# ENC28J60_Wing.net
KiCad netlist of a schematic drawn in EAGLE
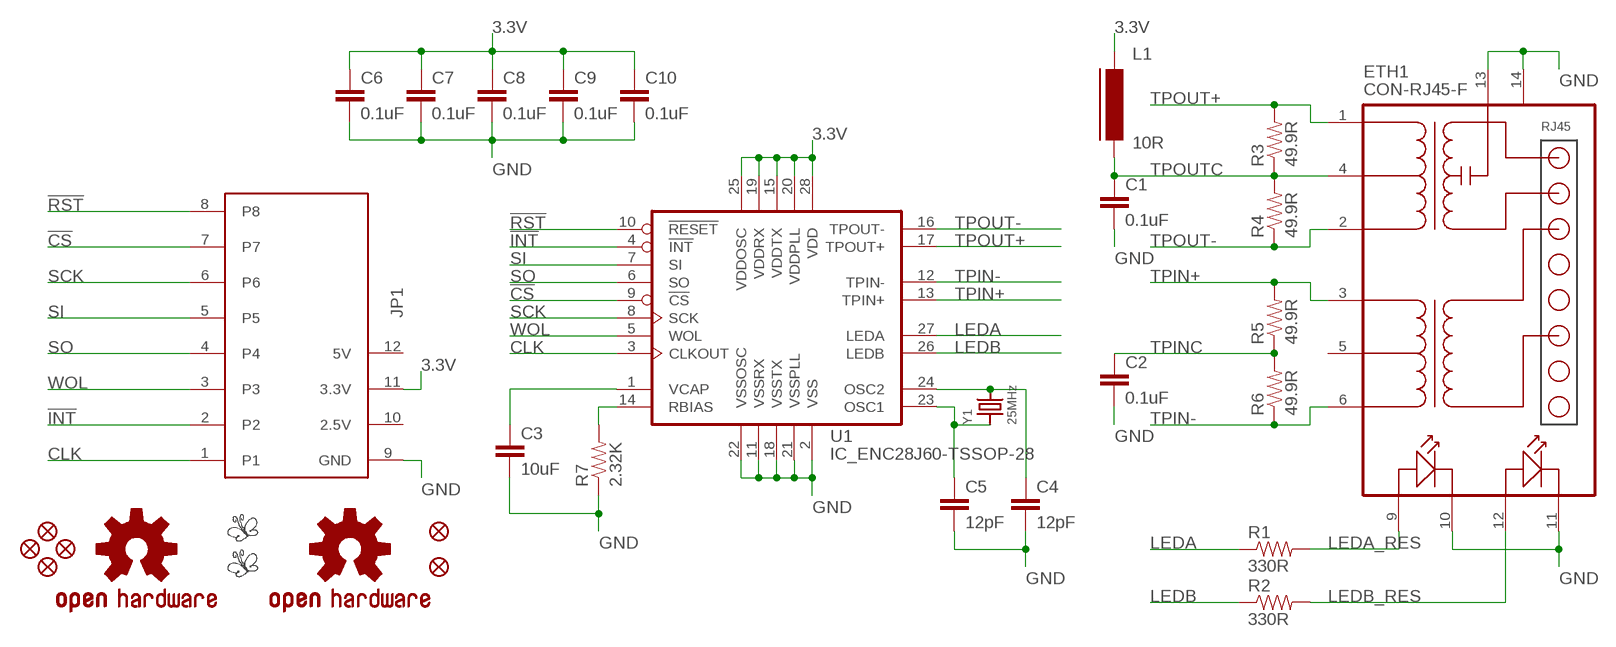
[diagram p0: schematic, sheet 1]

(export (version "E")
  (design (tool "Eeschema 10.0.6"))
  (components
    (comp (ref "C1")
      (value "0.1uF")
      (footprint "eagle-import:0402-CAP")
      (libsource (lib "eagle-import") (part "CAP0402-CAP"))
    )
    (comp (ref "C2")
      (value "0.1uF")
      (footprint "eagle-import:0402-CAP")
      (libsource (lib "eagle-import") (part "CAP0402-CAP"))
    )
    (comp (ref "C3")
      (value "10uF")
      (footprint "eagle-import:1206")
      (libsource (lib "eagle-import") (part "CAP1206"))
    )
    (comp (ref "C4")
      (value "12pF")
      (footprint "eagle-import:0402-CAP")
      (libsource (lib "eagle-import") (part "CAP0402-CAP"))
    )
    (comp (ref "C5")
      (value "12pF")
      (footprint "eagle-import:0402-CAP")
      (libsource (lib "eagle-import") (part "CAP0402-CAP"))
    )
    (comp (ref "C6")
      (value "0.1uF")
      (footprint "eagle-import:0402-CAP")
      (libsource (lib "eagle-import") (part "CAP0402-CAP"))
    )
    (comp (ref "C7")
      (value "0.1uF")
      (footprint "eagle-import:0402-CAP")
      (libsource (lib "eagle-import") (part "CAP0402-CAP"))
    )
    (comp (ref "C8")
      (value "0.1uF")
      (footprint "eagle-import:0402-CAP")
      (libsource (lib "eagle-import") (part "CAP0402-CAP"))
    )
    (comp (ref "C9")
      (value "0.1uF")
      (footprint "eagle-import:0402-CAP")
      (libsource (lib "eagle-import") (part "CAP0402-CAP"))
    )
    (comp (ref "C10")
      (value "0.1uF")
      (footprint "eagle-import:0402-CAP")
      (libsource (lib "eagle-import") (part "CAP0402-CAP"))
    )
    (comp (ref "ETH1")
      (value "CON-RJ45-F")
      (footprint "eagle-import:HR911105A")
      (libsource (lib "eagle-import") (part "CON-RJ45-F"))
    )
    (comp (ref "FID1")
      (value "FIDUCIALUFIDUCIAL")
      (footprint "eagle-import:MICRO-FIDUCIAL")
      (libsource (lib "eagle-import") (part "FIDUCIALUFIDUCIAL"))
    )
    (comp (ref "FID2")
      (value "FIDUCIALUFIDUCIAL")
      (footprint "eagle-import:MICRO-FIDUCIAL")
      (libsource (lib "eagle-import") (part "FIDUCIALUFIDUCIAL"))
    )
    (comp (ref "FID3")
      (value "FIDUCIALUFIDUCIAL")
      (footprint "eagle-import:MICRO-FIDUCIAL")
      (libsource (lib "eagle-import") (part "FIDUCIALUFIDUCIAL"))
    )
    (comp (ref "FID4")
      (value "FIDUCIALUFIDUCIAL")
      (footprint "eagle-import:MICRO-FIDUCIAL")
      (libsource (lib "eagle-import") (part "FIDUCIALUFIDUCIAL"))
    )
    (comp (ref "FID5")
      (value "FIDUCIALUFIDUCIAL")
      (footprint "eagle-import:MICRO-FIDUCIAL")
      (libsource (lib "eagle-import") (part "FIDUCIALUFIDUCIAL"))
    )
    (comp (ref "FID6")
      (value "FIDUCIALUFIDUCIAL")
      (footprint "eagle-import:MICRO-FIDUCIAL")
      (libsource (lib "eagle-import") (part "FIDUCIALUFIDUCIAL"))
    )
    (comp (ref "JP1")
      (value "PAPILIO-WING-8BITS")
      (footprint "eagle-import:PAPILIO-WING-8BITS")
      (libsource (lib "eagle-import") (part "PAPILIO-WING-8BITS"))
    )
    (comp (ref "L1")
      (value "10R")
      (footprint "eagle-import:FB402")
      (libsource (lib "eagle-import") (part "FERRITE-0402"))
    )
    (comp (ref "LOGO1")
      (value "BUTTERFLY_LOGO")
      (footprint "eagle-import:BUTTERFLY_LOGO")
      (libsource (lib "eagle-import") (part "BUTTERFLY_LOGO"))
    )
    (comp (ref "LOGO2")
      (value "BUTTERFLY_LOGO")
      (footprint "eagle-import:BUTTERFLY_LOGO")
      (libsource (lib "eagle-import") (part "BUTTERFLY_LOGO"))
    )
    (comp (ref "R1")
      (value "330R")
      (footprint "eagle-import:0402-RES")
      (libsource (lib "eagle-import") (part "RESISTOR0402-RES"))
    )
    (comp (ref "R2")
      (value "330R")
      (footprint "eagle-import:0402-RES")
      (libsource (lib "eagle-import") (part "RESISTOR0402-RES"))
    )
    (comp (ref "R3")
      (value "49.9R")
      (footprint "eagle-import:0402-RES")
      (libsource (lib "eagle-import") (part "RESISTOR0402-RES"))
    )
    (comp (ref "R4")
      (value "49.9R")
      (footprint "eagle-import:0402-RES")
      (libsource (lib "eagle-import") (part "RESISTOR0402-RES"))
    )
    (comp (ref "R5")
      (value "49.9R")
      (footprint "eagle-import:0402-RES")
      (libsource (lib "eagle-import") (part "RESISTOR0402-RES"))
    )
    (comp (ref "R6")
      (value "49.9R")
      (footprint "eagle-import:0402-RES")
      (libsource (lib "eagle-import") (part "RESISTOR0402-RES"))
    )
    (comp (ref "R7")
      (value "2.32K")
      (footprint "eagle-import:0402-RES")
      (libsource (lib "eagle-import") (part "RESISTOR0402-RES"))
    )
    (comp (ref "U$2")
      (value "OSHW-LOGOS")
      (footprint "eagle-import:OSHW-LOGO-S")
      (libsource (lib "eagle-import") (part "OSHW-LOGOS"))
    )
    (comp (ref "U$3")
      (value "OSHW-LOGOS")
      (footprint "eagle-import:OSHW-LOGO-S")
      (libsource (lib "eagle-import") (part "OSHW-LOGOS"))
    )
    (comp (ref "U1")
      (value "IC_ENC28J60-TSSOP-28")
      (footprint "eagle-import:TSSOP-28")
      (libsource (lib "eagle-import") (part "IC_ENC28J60-TSSOP-28"))
    )
    (comp (ref "Y1")
      (value "25MHz")
      (footprint "eagle-import:CRYSTAL_2.5X2")
      (libsource (lib "eagle-import") (part "CRYSTAL2.5X2.0MM"))
    )
  )
  (nets
    (net (code "1") (name "/3.3V") (class "Default")
      (node (ref "C10") (pin "1") (pinfunction "1_1") (pintype "passive"))
      (node (ref "C6") (pin "1") (pinfunction "1_1") (pintype "passive"))
      (node (ref "C7") (pin "1") (pinfunction "1_1") (pintype "passive"))
      (node (ref "C8") (pin "1") (pinfunction "1_1") (pintype "passive"))
      (node (ref "C9") (pin "1") (pinfunction "1_1") (pintype "passive"))
      (node (ref "JP1") (pin "11") (pinfunction "3.3V_11") (pintype "bidirectional"))
      (node (ref "L1") (pin "1") (pinfunction "1_1") (pintype "passive"))
      (node (ref "U1") (pin "15") (pinfunction "VDDTX_15") (pintype "power_in"))
      (node (ref "U1") (pin "19") (pinfunction "VDDRX_19") (pintype "power_in"))
      (node (ref "U1") (pin "20") (pinfunction "VDDPLL_20") (pintype "power_in"))
      (node (ref "U1") (pin "25") (pinfunction "VDDOSC_25") (pintype "power_in"))
      (node (ref "U1") (pin "28") (pinfunction "VDD_28") (pintype "power_in"))
    )
    (net (code "2") (name "/CLK") (class "Default")
      (node (ref "JP1") (pin "1") (pinfunction "P1_1") (pintype "bidirectional"))
      (node (ref "U1") (pin "3") (pinfunction "CLKOUT_3") (pintype "output"))
    )
    (net (code "3") (name "/GND") (class "Default")
      (node (ref "C1") (pin "2") (pinfunction "2_2") (pintype "passive"))
      (node (ref "C10") (pin "2") (pinfunction "2_2") (pintype "passive"))
      (node (ref "C2") (pin "2") (pinfunction "2_2") (pintype "passive"))
      (node (ref "C3") (pin "2") (pinfunction "2_2") (pintype "passive"))
      (node (ref "C4") (pin "2") (pinfunction "2_2") (pintype "passive"))
      (node (ref "C5") (pin "2") (pinfunction "2_2") (pintype "passive"))
      (node (ref "C6") (pin "2") (pinfunction "2_2") (pintype "passive"))
      (node (ref "C7") (pin "2") (pinfunction "2_2") (pintype "passive"))
      (node (ref "C8") (pin "2") (pinfunction "2_2") (pintype "passive"))
      (node (ref "C9") (pin "2") (pinfunction "2_2") (pintype "passive"))
      (node (ref "ETH1") (pin "10") (pinfunction "10_10") (pintype "bidirectional"))
      (node (ref "ETH1") (pin "11") (pinfunction "11_11") (pintype "bidirectional"))
      (node (ref "ETH1") (pin "13") (pinfunction "13_13") (pintype "bidirectional"))
      (node (ref "ETH1") (pin "14") (pinfunction "14_14") (pintype "bidirectional"))
      (node (ref "JP1") (pin "9") (pinfunction "GND_9") (pintype "bidirectional"))
      (node (ref "R7") (pin "1") (pinfunction "1_1") (pintype "passive"))
      (node (ref "U1") (pin "11") (pinfunction "VSSRX_11") (pintype "power_in"))
      (node (ref "U1") (pin "18") (pinfunction "VSSTX_18") (pintype "power_in"))
      (node (ref "U1") (pin "2") (pinfunction "VSS_2") (pintype "power_in"))
      (node (ref "U1") (pin "21") (pinfunction "VSSPLL_21") (pintype "power_in"))
      (node (ref "U1") (pin "22") (pinfunction "VSSOSC_22") (pintype "power_in"))
    )
    (net (code "4") (name "/LEDA") (class "Default")
      (node (ref "R1") (pin "1") (pinfunction "1_1") (pintype "passive"))
      (node (ref "U1") (pin "27") (pinfunction "LEDA_27") (pintype "output"))
    )
    (net (code "5") (name "/LEDA_RES") (class "Default")
      (node (ref "ETH1") (pin "9") (pinfunction "9_9") (pintype "bidirectional"))
      (node (ref "R1") (pin "2") (pinfunction "2_2") (pintype "passive"))
    )
    (net (code "6") (name "/LEDB") (class "Default")
      (node (ref "R2") (pin "1") (pinfunction "1_1") (pintype "passive"))
      (node (ref "U1") (pin "26") (pinfunction "LEDB_26") (pintype "output"))
    )
    (net (code "7") (name "/LEDB_RES") (class "Default")
      (node (ref "ETH1") (pin "12") (pinfunction "12_12") (pintype "bidirectional"))
      (node (ref "R2") (pin "2") (pinfunction "2_2") (pintype "passive"))
    )
    (net (code "8") (name "/SCK") (class "Default")
      (node (ref "JP1") (pin "6") (pinfunction "P6_6") (pintype "bidirectional"))
      (node (ref "U1") (pin "8") (pinfunction "SCK_8") (pintype "input"))
    )
    (net (code "9") (name "/SI") (class "Default")
      (node (ref "JP1") (pin "5") (pinfunction "P5_5") (pintype "bidirectional"))
      (node (ref "U1") (pin "7") (pinfunction "SI_7") (pintype "input"))
    )
    (net (code "10") (name "/SO") (class "Default")
      (node (ref "JP1") (pin "4") (pinfunction "P4_4") (pintype "bidirectional"))
      (node (ref "U1") (pin "6") (pinfunction "SO_6") (pintype "output"))
    )
    (net (code "11") (name "/TPIN+") (class "Default")
      (node (ref "ETH1") (pin "3") (pinfunction "3_3") (pintype "bidirectional"))
      (node (ref "R5") (pin "2") (pinfunction "2_2") (pintype "passive"))
      (node (ref "U1") (pin "13") (pinfunction "TPIN+_13") (pintype "input"))
    )
    (net (code "12") (name "/TPIN-") (class "Default")
      (node (ref "ETH1") (pin "6") (pinfunction "6_6") (pintype "bidirectional"))
      (node (ref "R6") (pin "1") (pinfunction "1_1") (pintype "passive"))
      (node (ref "U1") (pin "12") (pinfunction "TPIN-_12") (pintype "input"))
    )
    (net (code "13") (name "/TPINC") (class "Default")
      (node (ref "C2") (pin "1") (pinfunction "1_1") (pintype "passive"))
      (node (ref "R5") (pin "1") (pinfunction "1_1") (pintype "passive"))
      (node (ref "R6") (pin "2") (pinfunction "2_2") (pintype "passive"))
    )
    (net (code "14") (name "/TPOUT+") (class "Default")
      (node (ref "ETH1") (pin "1") (pinfunction "1_1") (pintype "bidirectional"))
      (node (ref "R3") (pin "2") (pinfunction "2_2") (pintype "passive"))
      (node (ref "U1") (pin "17") (pinfunction "TPOUT+_17") (pintype "output"))
    )
    (net (code "15") (name "/TPOUT-") (class "Default")
      (node (ref "ETH1") (pin "2") (pinfunction "2_2") (pintype "bidirectional"))
      (node (ref "R4") (pin "1") (pinfunction "1_1") (pintype "passive"))
      (node (ref "U1") (pin "16") (pinfunction "TPOUT-_16") (pintype "output"))
    )
    (net (code "16") (name "/TPOUTC") (class "Default")
      (node (ref "C1") (pin "1") (pinfunction "1_1") (pintype "passive"))
      (node (ref "ETH1") (pin "4") (pinfunction "4_4") (pintype "bidirectional"))
      (node (ref "L1") (pin "2") (pinfunction "2_2") (pintype "passive"))
      (node (ref "R3") (pin "1") (pinfunction "1_1") (pintype "passive"))
      (node (ref "R4") (pin "2") (pinfunction "2_2") (pintype "passive"))
    )
    (net (code "17") (name "/WOL") (class "Default")
      (node (ref "JP1") (pin "3") (pinfunction "P3_3") (pintype "bidirectional"))
      (node (ref "U1") (pin "5") (pinfunction "WOL_5") (pintype "bidirectional"))
    )
    (net (code "18") (name "/~{CS}") (class "Default")
      (node (ref "JP1") (pin "7") (pinfunction "P7_7") (pintype "bidirectional"))
      (node (ref "U1") (pin "9") (pinfunction "~{CS}_9") (pintype "input"))
    )
    (net (code "19") (name "/~{INT}") (class "Default")
      (node (ref "JP1") (pin "2") (pinfunction "P2_2") (pintype "bidirectional"))
      (node (ref "U1") (pin "4") (pinfunction "~{INT}_4") (pintype "output"))
    )
    (net (code "20") (name "/~{RST}") (class "Default")
      (node (ref "JP1") (pin "8") (pinfunction "P8_8") (pintype "bidirectional"))
      (node (ref "U1") (pin "10") (pinfunction "~{RESET}_10") (pintype "input"))
    )
    (net (code "21") (name "Net-(U1-OSC1)") (class "Default")
      (node (ref "C5") (pin "1") (pinfunction "1_1") (pintype "passive"))
      (node (ref "U1") (pin "23") (pinfunction "OSC1_23") (pintype "input"))
      (node (ref "Y1") (pin "1") (pinfunction "1_1") (pintype "passive"))
    )
    (net (code "22") (name "Net-(U1-OSC2)") (class "Default")
      (node (ref "C4") (pin "1") (pinfunction "1_1") (pintype "passive"))
      (node (ref "U1") (pin "24") (pinfunction "OSC2_24") (pintype "output"))
      (node (ref "Y1") (pin "3") (pinfunction "2_3") (pintype "passive"))
    )
    (net (code "23") (name "Net-(U1-RBIAS)") (class "Default")
      (node (ref "R7") (pin "2") (pinfunction "2_2") (pintype "passive"))
      (node (ref "U1") (pin "14") (pinfunction "RBIAS_14") (pintype "input"))
    )
    (net (code "24") (name "Net-(U1-VCAP)") (class "Default")
      (node (ref "C3") (pin "1") (pinfunction "1_1") (pintype "passive"))
      (node (ref "U1") (pin "1") (pinfunction "VCAP_1") (pintype "input"))
    )
    (net (code "25") (name "unconnected-(ETH1-Pad5)") (class "Default")
      (node (ref "ETH1") (pin "5") (pinfunction "5_5") (pintype "bidirectional"))
    )
    (net (code "26") (name "unconnected-(JP1-2.5V-Pad10)") (class "Default")
      (node (ref "JP1") (pin "10") (pinfunction "2.5V_10") (pintype "bidirectional"))
    )
    (net (code "27") (name "unconnected-(JP1-5V-Pad12)") (class "Default")
      (node (ref "JP1") (pin "12") (pinfunction "5V_12") (pintype "bidirectional"))
    )
  )
)
